# EdisonCandle.net
KiCad netlist of a schematic drawn in EAGLE
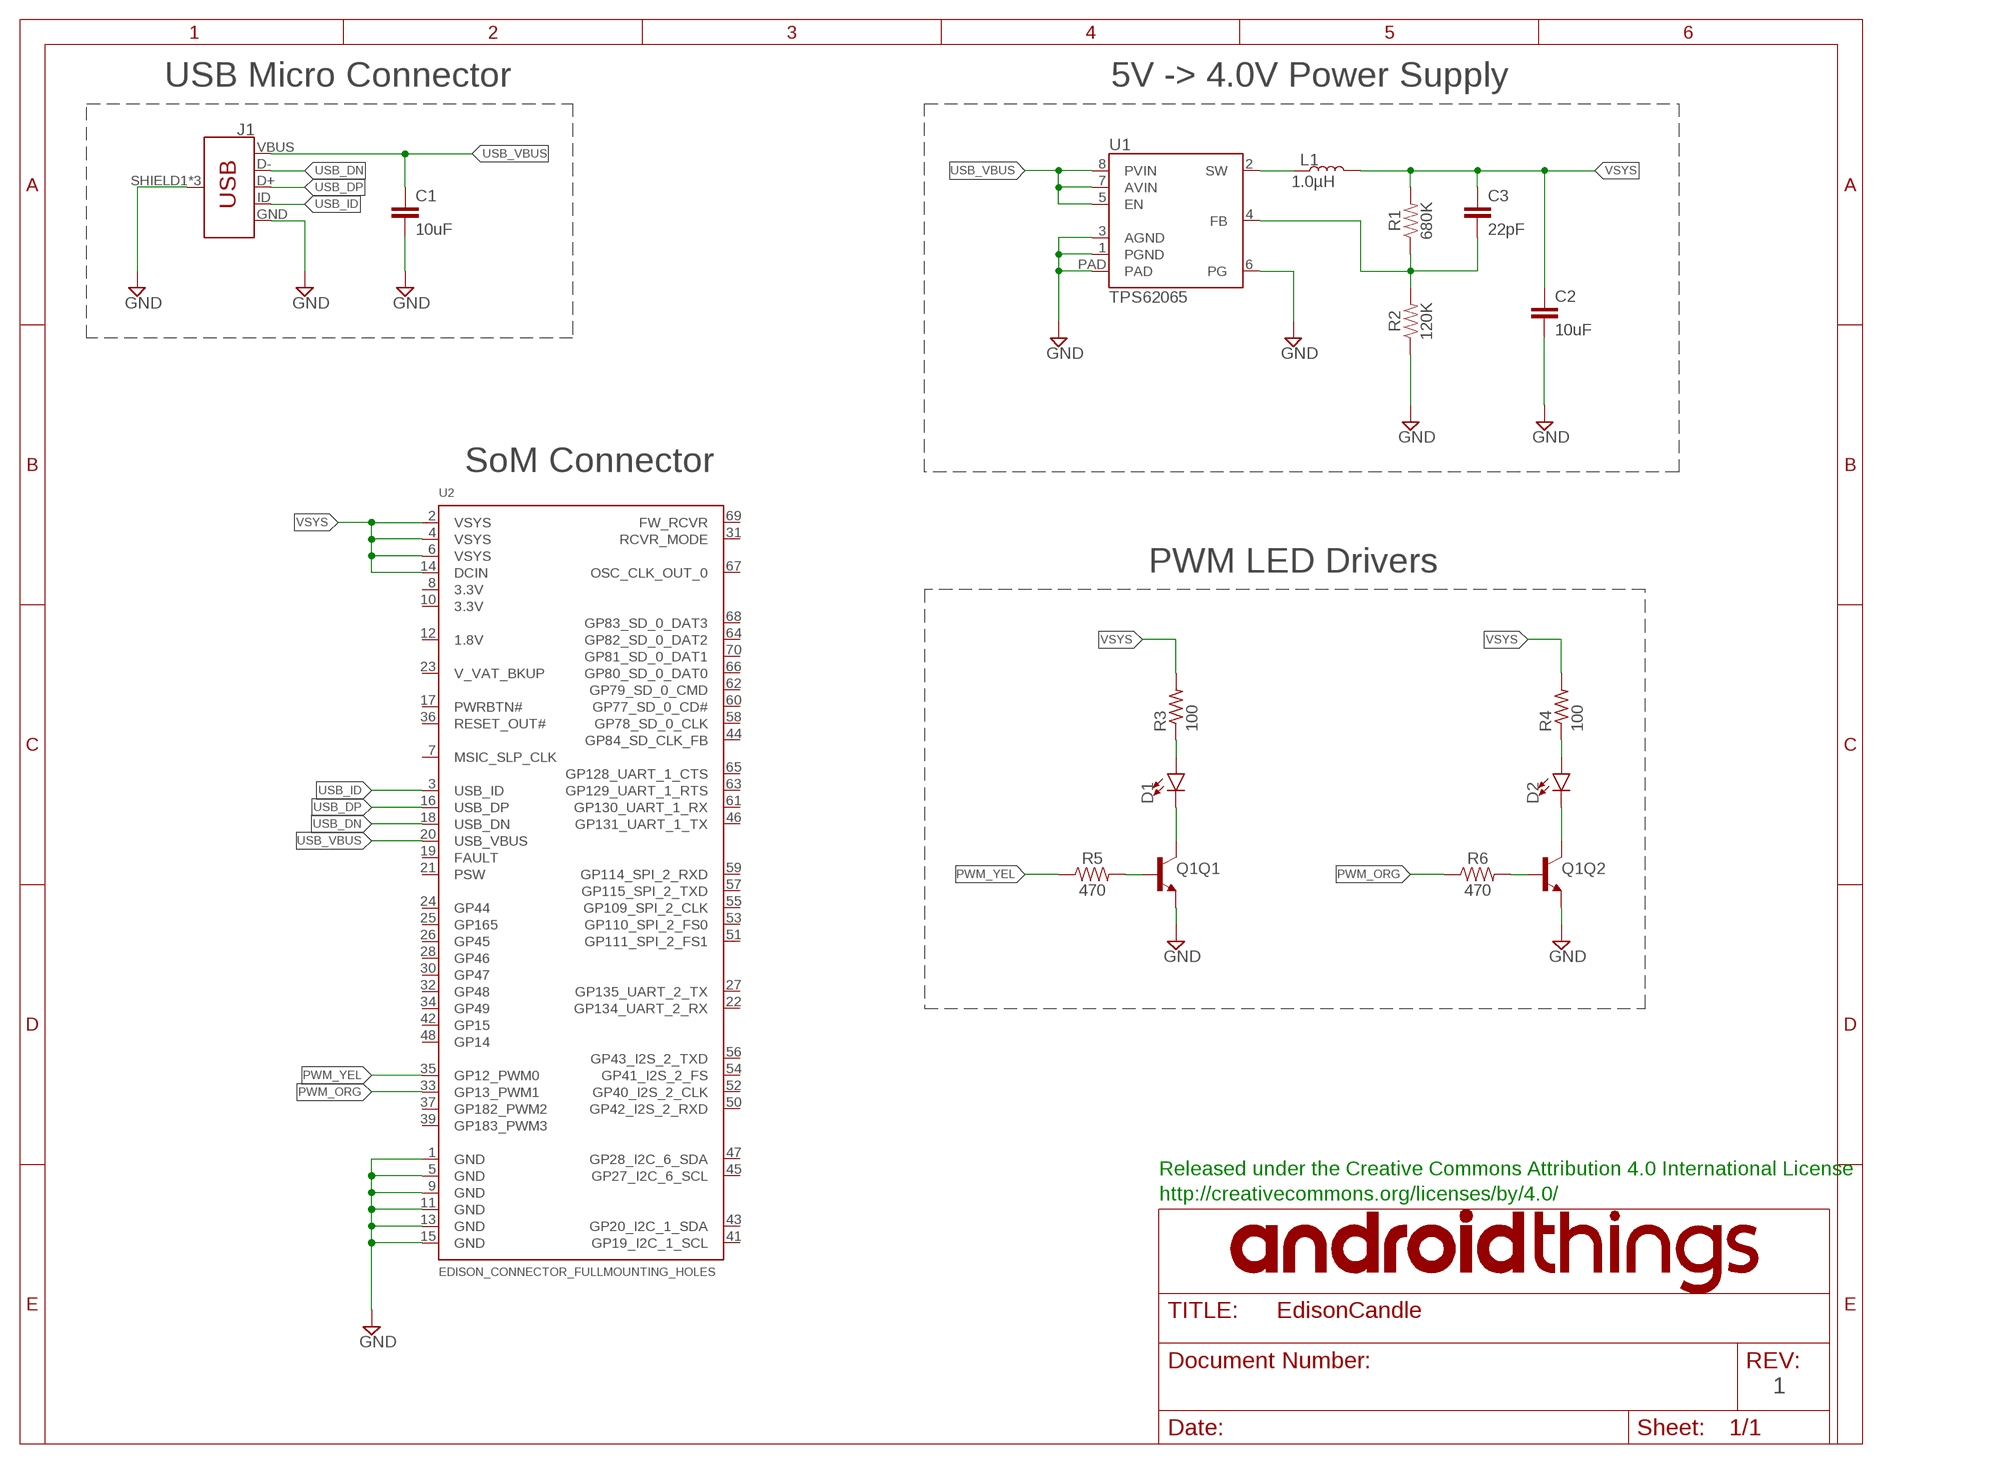
[diagram p0: schematic, sheet 1]

(export (version "E")
  (design (tool "Eeschema 10.0.6"))
  (components
    (comp (ref "C1")
      (value "10uF")
      (footprint "eagle-import:0805")
      (fields (field (name "MPN") "GRM21BR71A106KE51K"))
      (libsource (lib "eagle-import") (part "10UF-0805-10V-10%"))
    )
    (comp (ref "C2")
      (value "10uF")
      (footprint "eagle-import:0805")
      (fields (field (name "MPN") "GRM21BR71A106KE51K"))
      (libsource (lib "eagle-import") (part "10UF-0805-10V-10%"))
    )
    (comp (ref "C3")
      (value "22pF")
      (footprint "eagle-import:0603")
      (fields (field (name "MPN") "06035C220JAT2A"))
      (libsource (lib "eagle-import") (part "22PF-0603-50V-5%"))
    )
    (comp (ref "D1")
      (value "LED10MM")
      (footprint "eagle-import:LED_10MM")
      (libsource (lib "eagle-import") (part "LED10MM"))
    )
    (comp (ref "D2")
      (value "LED10MM")
      (footprint "eagle-import:LED_10MM")
      (libsource (lib "eagle-import") (part "LED10MM"))
    )
    (comp (ref "J1")
      (value "USB_MICRO-B_FEMALE-SMT")
      (footprint "eagle-import:USB-B-MICRO-SMD")
      (fields (field (name "MPN") "10104110-0001LF"))
      (libsource (lib "eagle-import") (part "USB_MICRO-B_FEMALE-SMT"))
    )
    (comp (ref "L1")
      (value "1.0µH")
      (footprint "eagle-import:SRP4020")
      (fields (field (name "MPN") "SRP4020-1R0M"))
      (libsource (lib "eagle-import") (part "INDUCTOR-SRP4020-1UH"))
    )
    (comp (ref "Q1")
      (value "TRANS_NPN_DUAL-MBT3904DW1T1")
      (footprint "eagle-import:SC70-6")
      (fields (field (name "MPN") "MBT3904DW1T1G"))
      (libsource (lib "eagle-import") (part "TRANS_NPN_DUAL-MBT3904DW1T1"))
    )
    (comp (ref "R1")
      (value "680K")
      (footprint "eagle-import:0603")
      (fields (field (name "MPN") "ERJ-3EKF6803V"))
      (libsource (lib "eagle-import") (part "680OHM-0603-1/10W-5%"))
    )
    (comp (ref "R2")
      (value "120K")
      (footprint "eagle-import:0603")
      (fields (field (name "MPN") "ERJ-3EKF1203V"))
      (libsource (lib "eagle-import") (part "180OHM-0603-1/10W-1%"))
    )
    (comp (ref "R3")
      (value "100")
      (footprint "eagle-import:M1206")
      (fields (field (name "MPN") "RC1206FR-07100RL"))
      (libsource (lib "eagle-import") (part "R-US_M1206"))
    )
    (comp (ref "R4")
      (value "100")
      (footprint "eagle-import:M1206")
      (fields (field (name "MPN") "RC1206FR-07100RL"))
      (libsource (lib "eagle-import") (part "R-US_M1206"))
    )
    (comp (ref "R5")
      (value "470")
      (footprint "eagle-import:0603")
      (fields (field (name "MPN") "ERJ-3EKF4700V"))
      (libsource (lib "eagle-import") (part "470OHM-0603-1/10W-1%"))
    )
    (comp (ref "R6")
      (value "470")
      (footprint "eagle-import:0603")
      (fields (field (name "MPN") "ERJ-3EKF4700V"))
      (libsource (lib "eagle-import") (part "470OHM-0603-1/10W-1%"))
    )
    (comp (ref "U1")
      (value "TPS62065")
      (footprint "eagle-import:WSON-8-PAD")
      (fields (field (name "MPN") "TPS62065DSGR"))
      (libsource (lib "eagle-import") (part "TPS62065"))
    )
    (comp (ref "U2")
      (value "EDISON_CONNECTOR_FULLMOUNTING_HOLES")
      (footprint "eagle-import:EDISON_DAUGHTER")
      (fields (field (name "MPN") "DF40HC(3.0)-70DS-0.4V(58)"))
      (libsource (lib "eagle-import") (part "EDISON_CONNECTOR_FULLMOUNTING_HOLES"))
    )
  )
  (nets
    (net (code "1") (name "GND") (class "Default")
      (node (ref "C1") (pin "2") (pinfunction "2_2") (pintype "passive"))
      (node (ref "C2") (pin "2") (pinfunction "2_2") (pintype "passive"))
      (node (ref "J1") (pin "GND") (pinfunction "GND_GND") (pintype "power_in"))
      (node (ref "J1") (pin "SHIELD1") (pinfunction "SHIELD_SHIELD1") (pintype "bidirectional"))
      (node (ref "J1") (pin "SHIELD2") (pinfunction "SHIELD_SHIELD2") (pintype "bidirectional"))
      (node (ref "J1") (pin "SHIELD3") (pinfunction "SHIELD_SHIELD3") (pintype "bidirectional"))
      (node (ref "Q1") (pin "1") (pinfunction "E_1") (pintype "passive"))
      (node (ref "Q1") (pin "4") (pinfunction "E_4") (pintype "passive"))
      (node (ref "R2") (pin "1") (pinfunction "1_1") (pintype "passive"))
      (node (ref "U1") (pin "1") (pinfunction "PGND_1") (pintype "bidirectional"))
      (node (ref "U1") (pin "3") (pinfunction "AGND_3") (pintype "bidirectional"))
      (node (ref "U1") (pin "6") (pinfunction "PG_6") (pintype "bidirectional"))
      (node (ref "U1") (pin "PAD") (pinfunction "PAD_PAD") (pintype "bidirectional"))
      (node (ref "U2") (pin "1") (pinfunction "GND_1") (pintype "bidirectional"))
      (node (ref "U2") (pin "11") (pinfunction "GND_11") (pintype "bidirectional"))
      (node (ref "U2") (pin "13") (pinfunction "GND_13") (pintype "bidirectional"))
      (node (ref "U2") (pin "15") (pinfunction "GND_15") (pintype "bidirectional"))
      (node (ref "U2") (pin "5") (pinfunction "GND_5") (pintype "bidirectional"))
      (node (ref "U2") (pin "9") (pinfunction "GND_9") (pintype "bidirectional"))
    )
    (net (code "2") (name "Net-(D1-PadA)") (class "Default")
      (node (ref "D1") (pin "A") (pinfunction "A_A") (pintype "passive"))
      (node (ref "R3") (pin "1") (pinfunction "1_1") (pintype "passive"))
    )
    (net (code "3") (name "Net-(D2-PadA)") (class "Default")
      (node (ref "D2") (pin "A") (pinfunction "A_A") (pintype "passive"))
      (node (ref "R4") (pin "1") (pinfunction "1_1") (pintype "passive"))
    )
    (net (code "4") (name "Net-(Q1A-B)") (class "Default")
      (node (ref "Q1") (pin "5") (pinfunction "B_5") (pintype "passive"))
      (node (ref "R5") (pin "2") (pinfunction "2_2") (pintype "passive"))
    )
    (net (code "5") (name "Net-(Q1A-C)") (class "Default")
      (node (ref "D1") (pin "C") (pinfunction "C_C") (pintype "passive"))
      (node (ref "Q1") (pin "3") (pinfunction "C_3") (pintype "passive"))
    )
    (net (code "6") (name "Net-(Q1B-B)") (class "Default")
      (node (ref "Q1") (pin "2") (pinfunction "B_2") (pintype "passive"))
      (node (ref "R6") (pin "2") (pinfunction "2_2") (pintype "passive"))
    )
    (net (code "7") (name "Net-(Q1B-C)") (class "Default")
      (node (ref "D2") (pin "C") (pinfunction "C_C") (pintype "passive"))
      (node (ref "Q1") (pin "6") (pinfunction "C_6") (pintype "passive"))
    )
    (net (code "8") (name "Net-(U1-FB)") (class "Default")
      (node (ref "C3") (pin "2") (pinfunction "2_2") (pintype "passive"))
      (node (ref "R1") (pin "1") (pinfunction "1_1") (pintype "passive"))
      (node (ref "R2") (pin "2") (pinfunction "2_2") (pintype "passive"))
      (node (ref "U1") (pin "4") (pinfunction "FB_4") (pintype "bidirectional"))
    )
    (net (code "9") (name "Net-(U1-SW)") (class "Default")
      (node (ref "L1") (pin "1") (pinfunction "1_1") (pintype "passive"))
      (node (ref "U1") (pin "2") (pinfunction "SW_2") (pintype "bidirectional"))
    )
    (net (code "10") (name "PWM_ORG") (class "Default")
      (node (ref "R6") (pin "1") (pinfunction "1_1") (pintype "passive"))
      (node (ref "U2") (pin "33") (pinfunction "GP13_PWM1_33") (pintype "bidirectional"))
    )
    (net (code "11") (name "PWM_YEL") (class "Default")
      (node (ref "R5") (pin "1") (pinfunction "1_1") (pintype "passive"))
      (node (ref "U2") (pin "35") (pinfunction "GP12_PWM0_35") (pintype "bidirectional"))
    )
    (net (code "12") (name "USB_DN") (class "Default")
      (node (ref "J1") (pin "D-") (pinfunction "D-_D-") (pintype "bidirectional"))
      (node (ref "U2") (pin "18") (pinfunction "USB_DN_18") (pintype "bidirectional"))
    )
    (net (code "13") (name "USB_DP") (class "Default")
      (node (ref "J1") (pin "D+") (pinfunction "D+_D+") (pintype "bidirectional"))
      (node (ref "U2") (pin "16") (pinfunction "USB_DP_16") (pintype "bidirectional"))
    )
    (net (code "14") (name "USB_ID") (class "Default")
      (node (ref "J1") (pin "ID") (pinfunction "ID_ID") (pintype "bidirectional"))
      (node (ref "U2") (pin "3") (pinfunction "USB_ID_3") (pintype "bidirectional"))
    )
    (net (code "15") (name "USB_VBUS") (class "Default")
      (node (ref "C1") (pin "1") (pinfunction "1_1") (pintype "passive"))
      (node (ref "J1") (pin "VBUS") (pinfunction "VBUS_VBUS") (pintype "power_in"))
      (node (ref "U1") (pin "5") (pinfunction "EN_5") (pintype "bidirectional"))
      (node (ref "U1") (pin "7") (pinfunction "AVIN_7") (pintype "bidirectional"))
      (node (ref "U1") (pin "8") (pinfunction "PVIN_8") (pintype "bidirectional"))
      (node (ref "U2") (pin "20") (pinfunction "USB_VBUS_20") (pintype "bidirectional"))
    )
    (net (code "16") (name "VSYS") (class "Default")
      (node (ref "C2") (pin "1") (pinfunction "1_1") (pintype "passive"))
      (node (ref "C3") (pin "1") (pinfunction "1_1") (pintype "passive"))
      (node (ref "L1") (pin "2") (pinfunction "2_2") (pintype "passive"))
      (node (ref "R1") (pin "2") (pinfunction "2_2") (pintype "passive"))
      (node (ref "R3") (pin "2") (pinfunction "2_2") (pintype "passive"))
      (node (ref "R4") (pin "2") (pinfunction "2_2") (pintype "passive"))
      (node (ref "U2") (pin "14") (pinfunction "DCIN_14") (pintype "bidirectional"))
      (node (ref "U2") (pin "2") (pinfunction "VSYS_2") (pintype "bidirectional"))
      (node (ref "U2") (pin "4") (pinfunction "VSYS_4") (pintype "bidirectional"))
      (node (ref "U2") (pin "6") (pinfunction "VSYS_6") (pintype "bidirectional"))
    )
    (net (code "17") (name "unconnected-(U2-1.8V-Pad12)") (class "Default")
      (node (ref "U2") (pin "12") (pinfunction "1.8V_12") (pintype "bidirectional"))
    )
    (net (code "18") (name "unconnected-(U2-3.3V-Pad8)") (class "Default")
      (node (ref "U2") (pin "8") (pinfunction "3.3V_8") (pintype "bidirectional"))
    )
    (net (code "19") (name "unconnected-(U2-3.3V-Pad10)") (class "Default")
      (node (ref "U2") (pin "10") (pinfunction "3.3V_10") (pintype "bidirectional"))
    )
    (net (code "20") (name "unconnected-(U2-FAULT-Pad19)") (class "Default")
      (node (ref "U2") (pin "19") (pinfunction "FAULT_19") (pintype "bidirectional"))
    )
    (net (code "21") (name "unconnected-(U2-FW_RCVR-Pad69)") (class "Default")
      (node (ref "U2") (pin "69") (pinfunction "FW_RCVR_69") (pintype "bidirectional"))
    )
    (net (code "22") (name "unconnected-(U2-GP14-Pad48)") (class "Default")
      (node (ref "U2") (pin "48") (pinfunction "GP14_48") (pintype "bidirectional"))
    )
    (net (code "23") (name "unconnected-(U2-GP15-Pad42)") (class "Default")
      (node (ref "U2") (pin "42") (pinfunction "GP15_42") (pintype "bidirectional"))
    )
    (net (code "24") (name "unconnected-(U2-GP19_I2C_1_SCL-Pad41)") (class "Default")
      (node (ref "U2") (pin "41") (pinfunction "GP19_I2C_1_SCL_41") (pintype "bidirectional"))
    )
    (net (code "25") (name "unconnected-(U2-GP20_I2C_1_SDA-Pad43)") (class "Default")
      (node (ref "U2") (pin "43") (pinfunction "GP20_I2C_1_SDA_43") (pintype "bidirectional"))
    )
    (net (code "26") (name "unconnected-(U2-GP27_I2C_6_SCL-Pad45)") (class "Default")
      (node (ref "U2") (pin "45") (pinfunction "GP27_I2C_6_SCL_45") (pintype "bidirectional"))
    )
    (net (code "27") (name "unconnected-(U2-GP28_I2C_6_SDA-Pad47)") (class "Default")
      (node (ref "U2") (pin "47") (pinfunction "GP28_I2C_6_SDA_47") (pintype "bidirectional"))
    )
    (net (code "28") (name "unconnected-(U2-GP40_I2S_2_CLK-Pad52)") (class "Default")
      (node (ref "U2") (pin "52") (pinfunction "GP40_I2S_2_CLK_52") (pintype "bidirectional"))
    )
    (net (code "29") (name "unconnected-(U2-GP41_I2S_2_FS-Pad54)") (class "Default")
      (node (ref "U2") (pin "54") (pinfunction "GP41_I2S_2_FS_54") (pintype "bidirectional"))
    )
    (net (code "30") (name "unconnected-(U2-GP42_I2S_2_RXD-Pad50)") (class "Default")
      (node (ref "U2") (pin "50") (pinfunction "GP42_I2S_2_RXD_50") (pintype "bidirectional"))
    )
    (net (code "31") (name "unconnected-(U2-GP43_I2S_2_TXD-Pad56)") (class "Default")
      (node (ref "U2") (pin "56") (pinfunction "GP43_I2S_2_TXD_56") (pintype "bidirectional"))
    )
    (net (code "32") (name "unconnected-(U2-GP44-Pad24)") (class "Default")
      (node (ref "U2") (pin "24") (pinfunction "GP44_24") (pintype "bidirectional"))
    )
    (net (code "33") (name "unconnected-(U2-GP45-Pad26)") (class "Default")
      (node (ref "U2") (pin "26") (pinfunction "GP45_26") (pintype "bidirectional"))
    )
    (net (code "34") (name "unconnected-(U2-GP46-Pad28)") (class "Default")
      (node (ref "U2") (pin "28") (pinfunction "GP46_28") (pintype "bidirectional"))
    )
    (net (code "35") (name "unconnected-(U2-GP47-Pad30)") (class "Default")
      (node (ref "U2") (pin "30") (pinfunction "GP47_30") (pintype "bidirectional"))
    )
    (net (code "36") (name "unconnected-(U2-GP48-Pad32)") (class "Default")
      (node (ref "U2") (pin "32") (pinfunction "GP48_32") (pintype "bidirectional"))
    )
    (net (code "37") (name "unconnected-(U2-GP49-Pad34)") (class "Default")
      (node (ref "U2") (pin "34") (pinfunction "GP49_34") (pintype "bidirectional"))
    )
    (net (code "38") (name "unconnected-(U2-GP77_SD_0_CD#-Pad60)") (class "Default")
      (node (ref "U2") (pin "60") (pinfunction "GP77_SD_0_CD#_60") (pintype "bidirectional"))
    )
    (net (code "39") (name "unconnected-(U2-GP78_SD_0_CLK-Pad58)") (class "Default")
      (node (ref "U2") (pin "58") (pinfunction "GP78_SD_0_CLK_58") (pintype "bidirectional"))
    )
    (net (code "40") (name "unconnected-(U2-GP79_SD_0_CMD-Pad62)") (class "Default")
      (node (ref "U2") (pin "62") (pinfunction "GP79_SD_0_CMD_62") (pintype "bidirectional"))
    )
    (net (code "41") (name "unconnected-(U2-GP80_SD_0_DAT0-Pad66)") (class "Default")
      (node (ref "U2") (pin "66") (pinfunction "GP80_SD_0_DAT0_66") (pintype "bidirectional"))
    )
    (net (code "42") (name "unconnected-(U2-GP81_SD_0_DAT1-Pad70)") (class "Default")
      (node (ref "U2") (pin "70") (pinfunction "GP81_SD_0_DAT1_70") (pintype "bidirectional"))
    )
    (net (code "43") (name "unconnected-(U2-GP82_SD_0_DAT2-Pad64)") (class "Default")
      (node (ref "U2") (pin "64") (pinfunction "GP82_SD_0_DAT2_64") (pintype "bidirectional"))
    )
    (net (code "44") (name "unconnected-(U2-GP83_SD_0_DAT3-Pad68)") (class "Default")
      (node (ref "U2") (pin "68") (pinfunction "GP83_SD_0_DAT3_68") (pintype "bidirectional"))
    )
    (net (code "45") (name "unconnected-(U2-GP84_SD_CLK_FB-Pad44)") (class "Default")
      (node (ref "U2") (pin "44") (pinfunction "GP84_SD_CLK_FB_44") (pintype "bidirectional"))
    )
    (net (code "46") (name "unconnected-(U2-GP109_SPI_2_CLK-Pad55)") (class "Default")
      (node (ref "U2") (pin "55") (pinfunction "GP109_SPI_2_CLK_55") (pintype "bidirectional"))
    )
    (net (code "47") (name "unconnected-(U2-GP110_SPI_2_FS0-Pad53)") (class "Default")
      (node (ref "U2") (pin "53") (pinfunction "GP110_SPI_2_FS0_53") (pintype "bidirectional"))
    )
    (net (code "48") (name "unconnected-(U2-GP111_SPI_2_FS1-Pad51)") (class "Default")
      (node (ref "U2") (pin "51") (pinfunction "GP111_SPI_2_FS1_51") (pintype "bidirectional"))
    )
    (net (code "49") (name "unconnected-(U2-GP114_SPI_2_RXD-Pad59)") (class "Default")
      (node (ref "U2") (pin "59") (pinfunction "GP114_SPI_2_RXD_59") (pintype "bidirectional"))
    )
    (net (code "50") (name "unconnected-(U2-GP115_SPI_2_TXD-Pad57)") (class "Default")
      (node (ref "U2") (pin "57") (pinfunction "GP115_SPI_2_TXD_57") (pintype "bidirectional"))
    )
    (net (code "51") (name "unconnected-(U2-GP128_UART_1_CTS-Pad65)") (class "Default")
      (node (ref "U2") (pin "65") (pinfunction "GP128_UART_1_CTS_65") (pintype "bidirectional"))
    )
    (net (code "52") (name "unconnected-(U2-GP129_UART_1_RTS-Pad63)") (class "Default")
      (node (ref "U2") (pin "63") (pinfunction "GP129_UART_1_RTS_63") (pintype "bidirectional"))
    )
    (net (code "53") (name "unconnected-(U2-GP130_UART_1_RX-Pad61)") (class "Default")
      (node (ref "U2") (pin "61") (pinfunction "GP130_UART_1_RX_61") (pintype "bidirectional"))
    )
    (net (code "54") (name "unconnected-(U2-GP131_UART_1_TX-Pad46)") (class "Default")
      (node (ref "U2") (pin "46") (pinfunction "GP131_UART_1_TX_46") (pintype "bidirectional"))
    )
    (net (code "55") (name "unconnected-(U2-GP134_UART_2_RX-Pad22)") (class "Default")
      (node (ref "U2") (pin "22") (pinfunction "GP134_UART_2_RX_22") (pintype "bidirectional"))
    )
    (net (code "56") (name "unconnected-(U2-GP135_UART_2_TX-Pad27)") (class "Default")
      (node (ref "U2") (pin "27") (pinfunction "GP135_UART_2_TX_27") (pintype "bidirectional"))
    )
    (net (code "57") (name "unconnected-(U2-GP165-Pad25)") (class "Default")
      (node (ref "U2") (pin "25") (pinfunction "GP165_25") (pintype "bidirectional"))
    )
    (net (code "58") (name "unconnected-(U2-GP182_PWM2-Pad37)") (class "Default")
      (node (ref "U2") (pin "37") (pinfunction "GP182_PWM2_37") (pintype "bidirectional"))
    )
    (net (code "59") (name "unconnected-(U2-GP183_PWM3-Pad39)") (class "Default")
      (node (ref "U2") (pin "39") (pinfunction "GP183_PWM3_39") (pintype "bidirectional"))
    )
    (net (code "60") (name "unconnected-(U2-MSIC_SLP_CLK-Pad7)") (class "Default")
      (node (ref "U2") (pin "7") (pinfunction "MSIC_SLP_CLK_7") (pintype "bidirectional"))
    )
    (net (code "61") (name "unconnected-(U2-OSC_CLK_OUT_0-Pad67)") (class "Default")
      (node (ref "U2") (pin "67") (pinfunction "OSC_CLK_OUT_0_67") (pintype "bidirectional"))
    )
    (net (code "62") (name "unconnected-(U2-PSW-Pad21)") (class "Default")
      (node (ref "U2") (pin "21") (pinfunction "PSW_21") (pintype "bidirectional"))
    )
    (net (code "63") (name "unconnected-(U2-PWRBTN#-Pad17)") (class "Default")
      (node (ref "U2") (pin "17") (pinfunction "PWRBTN#_17") (pintype "bidirectional"))
    )
    (net (code "64") (name "unconnected-(U2-RCVR_MODE-Pad31)") (class "Default")
      (node (ref "U2") (pin "31") (pinfunction "RCVR_MODE_31") (pintype "bidirectional"))
    )
    (net (code "65") (name "unconnected-(U2-RESET_OUT#-Pad36)") (class "Default")
      (node (ref "U2") (pin "36") (pinfunction "RESET_OUT#_36") (pintype "bidirectional"))
    )
    (net (code "66") (name "unconnected-(U2-V_VAT_BKUP-Pad23)") (class "Default")
      (node (ref "U2") (pin "23") (pinfunction "V_VAT_BKUP_23") (pintype "bidirectional"))
    )
  )
)
